# dcdc_60v_12v.net
KiCad netlist of a schematic drawn in Altium Designer
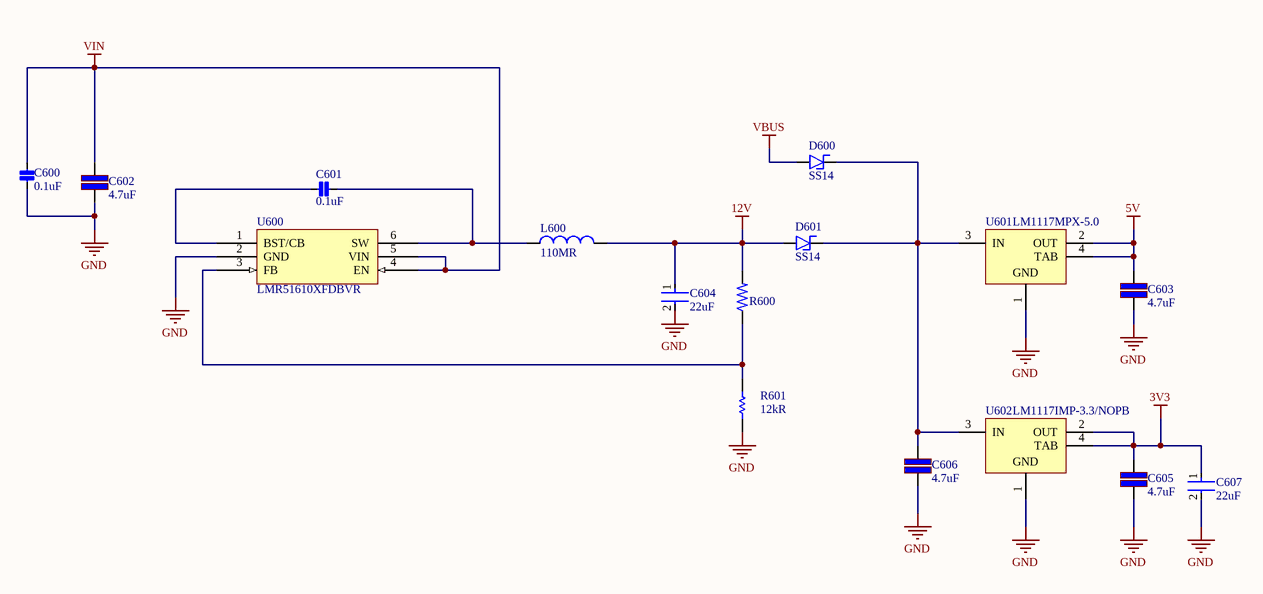
[diagram p0: dcdc_60v_12v.SchDoc]

(export (version "E")
  (design (tool "Eeschema 10.0.6"))
  (components
    (comp (ref "C600")
      (value "0.1uF")
      (footprint "FP-CL10-IPC_B")
      (description "Cap Ceramic 0.1uF 50V X7R 20% SMD 0603 125C Paper T/R")
      (fields (field (name "VOLTAGE") "50V") (field (name "Comment") "CAP 0.1uF 50V X7R 0603"))
      (libsource (lib "") (part "C-EU_1"))
    )
    (comp (ref "C601")
      (value "0.1uF")
      (footprint "FP-CL10-IPC_B")
      (description "Cap Ceramic 0.1uF 50V X7R 20% SMD 0603 125C Paper T/R")
      (fields (field (name "VOLTAGE") "50V") (field (name "Comment") "CAP 0.1uF 50V X7R 0603"))
      (libsource (lib "StackFoundry LLC") (part "C-EU"))
    )
    (comp (ref "C602")
      (value "4.7uF")
      (footprint "CAPC3225X20N")
      (description "CAP CER 4.7UF 50V X7R 1210")
      (fields (field (name "VOLTAGE") "50V") (field (name "TOLERANCE") "10%"))
      (libsource (lib "StackFoundry LLC") (part "4.7uF"))
    )
    (comp (ref "C603")
      (value "4.7uF")
      (footprint "CAPC3225X20N")
      (description "CAP CER 4.7UF 50V X7R 1210")
      (fields (field (name "VOLTAGE") "50V") (field (name "TOLERANCE") "10%"))
      (libsource (lib "StackFoundry LLC") (part "4.7uF"))
    )
    (comp (ref "C604")
      (value "22uF")
      (footprint "FP-1210-L_3_2_0_3-W_2_5_0-MFG")
      (description "1210 22 uF 25 V ±20% Tolerance X7R Multilayer Ceramic Chip Capacitor")
      (fields (field (name "TOLERANCE") "20%") (field (name "Comment") "CAP 22uF 25V 1210 X7R"))
      (libsource (lib "StackFoundry LLC") (part "02cd4be3c70576c341d710602a673aa"))
    )
    (comp (ref "C605")
      (value "4.7uF")
      (footprint "CAPC3225X20N")
      (description "CAP CER 4.7UF 50V X7R 1210")
      (fields (field (name "VOLTAGE") "50V") (field (name "TOLERANCE") "10%"))
      (libsource (lib "StackFoundry LLC") (part "4.7uF"))
    )
    (comp (ref "C606")
      (value "4.7uF")
      (footprint "CAPC3225X20N")
      (description "CAP CER 4.7UF 50V X7R 1210")
      (fields (field (name "VOLTAGE") "50V") (field (name "TOLERANCE") "10%"))
      (libsource (lib "StackFoundry LLC") (part "4.7uF"))
    )
    (comp (ref "C607")
      (value "22uF")
      (footprint "FP-1210-L_3_2_0_3-W_2_5_0-MFG")
      (description "1210 22 uF 25 V ±20% Tolerance X7R Multilayer Ceramic Chip Capacitor")
      (fields (field (name "TOLERANCE") "20%") (field (name "Comment") "CAP 22uF 25V 1210 X7R"))
      (libsource (lib "StackFoundry LLC") (part "02cd4be3c70576c341d710602a673aa"))
    )
    (comp (ref "D600")
      (value "SS14")
      (footprint "SMA")
      (libsource (lib "StackFoundry LLC") (part "DIODE_SCHOTTKY"))
    )
    (comp (ref "D601")
      (value "SS14")
      (footprint "SMA")
      (libsource (lib "StackFoundry LLC") (part "DIODE_SCHOTTKY"))
    )
    (comp (ref "L600")
      (value "110MR")
      (footprint "SRR1260-680M-Footprint-1")
      (description "Ind Power Shielded Wirewound 68uH 20% 100KHz 22Q-Factor Ferrite 2.1A T/R")
      (fields (field (name "TOLERANCE") "20%") (field (name "Comment") "SRR1260-680M"))
      (libsource (lib "StackFoundry LLC") (part "L-US"))
    )
    (comp (ref "R600")
      (value "100k 0603 1%")
      (footprint "RESC1608-IPC-LL")
      (description "Res Thick Film 1.6 x 0.8 mm 100K Ohm 1% 0.1W(1/10W) 100ppm/ C Molded SMD Paper T/R")
      (libsource (lib "StackFoundry LLC") (part "R-US"))
    )
    (comp (ref "R601")
      (value "12kR")
      (footprint "RESC1608X55X25LL10T15")
      (description "SMD Chip Resistor, 12 kOhm, ± 1%, 100 mW, 0603 [1608 Metric], Thick Film, General Purpose")
      (fields (field (name "TOLERANCE") "1%") (field (name "Comment") "12k 0603 1%"))
      (libsource (lib "StackFoundry LLC") (part "RES-2"))
    )
    (comp (ref "U600")
      (value "LMR51610XFDBVR")
      (footprint "SOT95P280X145-6N")
      (libsource (lib "StackFoundry LLC") (part "LMR51610XFDBVR-Symbol-1"))
    )
    (comp (ref "U601")
      (value "LM1117MPX-5.0")
      (footprint "DCY0004A_M")
      (description "LDO Regulator Pos 5V 0.8A 4-Pin(3+Tab) SOT-223 T/R")
      (libsource (lib "StackFoundry LLC") (part "PM-REG-LM1086-SOT4"))
    )
    (comp (ref "U602")
      (value "LM1117IMP-3.3/NOPB")
      (footprint "DCY0004A_M")
      (description "LDO Regulator Pos 3.3V 0.8A 4-Pin(3+Tab) SOT-223 T/R / IC REG LDO 3.3V 0.8A SOT223")
      (libsource (lib "StackFoundry LLC") (part "PM-REG-LM1086-SOT4"))
    )
  )
  (nets
    (net (code "1") (name "3V3") (class "Default")
      (node (ref "C605") (pin "2") (pintype "passive"))
      (node (ref "C607") (pin "1") (pinfunction "1_1") (pintype "passive"))
      (node (ref "U602") (pin "2") (pinfunction "OUT_2") (pintype "power_in"))
      (node (ref "U602") (pin "4") (pinfunction "TAB_4") (pintype "power_in"))
    )
    (net (code "2") (name "5V") (class "Default")
      (node (ref "C603") (pin "2") (pintype "passive"))
      (node (ref "U601") (pin "2") (pinfunction "OUT_2") (pintype "power_in"))
      (node (ref "U601") (pin "4") (pinfunction "TAB_4") (pintype "power_in"))
    )
    (net (code "3") (name "12V") (class "Default")
      (node (ref "C604") (pin "1") (pinfunction "1_1") (pintype "passive"))
      (node (ref "D601") (pin "A") (pinfunction "A_A") (pintype "power_in"))
      (node (ref "L600") (pin "2") (pinfunction "2_2") (pintype "passive"))
      (node (ref "R600") (pin "2") (pinfunction "2_2") (pintype "passive"))
    )
    (net (code "4") (name "GND") (class "Default")
      (node (ref "C600") (pin "1") (pinfunction "1_1") (pintype "passive"))
      (node (ref "C602") (pin "1") (pintype "passive"))
      (node (ref "C603") (pin "1") (pintype "passive"))
      (node (ref "C604") (pin "2") (pinfunction "2_2") (pintype "passive"))
      (node (ref "C605") (pin "1") (pintype "passive"))
      (node (ref "C606") (pin "1") (pintype "passive"))
      (node (ref "C607") (pin "2") (pinfunction "2_2") (pintype "passive"))
      (node (ref "R601") (pin "1") (pinfunction "1_1") (pintype "passive"))
      (node (ref "U600") (pin "2") (pinfunction "GND_2") (pintype "power_in"))
      (node (ref "U601") (pin "1") (pinfunction "GND_1") (pintype "power_in"))
      (node (ref "U602") (pin "1") (pinfunction "GND_1") (pintype "power_in"))
    )
    (net (code "5") (name "Net-(U600-BST{slash}CB)") (class "Default")
      (node (ref "C601") (pin "1") (pinfunction "1_1") (pintype "passive"))
      (node (ref "U600") (pin "1") (pinfunction "BST/CB_1") (pintype "passive"))
    )
    (net (code "6") (name "Net-(U600-FB)") (class "Default")
      (node (ref "R600") (pin "1") (pinfunction "1_1") (pintype "passive"))
      (node (ref "R601") (pin "2") (pinfunction "2_2") (pintype "passive"))
      (node (ref "U600") (pin "3") (pinfunction "FB_3") (pintype "input"))
    )
    (net (code "7") (name "Net-(U600-SW)") (class "Default")
      (node (ref "C601") (pin "2") (pinfunction "2_2") (pintype "passive"))
      (node (ref "L600") (pin "1") (pinfunction "1_1") (pintype "passive"))
      (node (ref "U600") (pin "6") (pinfunction "SW_6") (pintype "passive"))
    )
    (net (code "8") (name "Net-(U601-IN)") (class "Default")
      (node (ref "C606") (pin "2") (pintype "passive"))
      (node (ref "D600") (pin "K") (pinfunction "K_K") (pintype "power_in"))
      (node (ref "D601") (pin "K") (pinfunction "K_K") (pintype "power_in"))
      (node (ref "U601") (pin "3") (pinfunction "IN_3") (pintype "power_in"))
      (node (ref "U602") (pin "3") (pinfunction "IN_3") (pintype "power_in"))
    )
    (net (code "9") (name "VBUS") (class "Default")
      (node (ref "D600") (pin "A") (pinfunction "A_A") (pintype "power_in"))
    )
    (net (code "10") (name "VIN") (class "Default")
      (node (ref "C600") (pin "2") (pinfunction "2_2") (pintype "passive"))
      (node (ref "C602") (pin "2") (pintype "passive"))
      (node (ref "U600") (pin "4") (pinfunction "EN_4") (pintype "input"))
      (node (ref "U600") (pin "5") (pinfunction "VIN_5") (pintype "power_in"))
    )
  )
)
